# hex_schmitt_CMOS.net
KiCad netlist of a schematic drawn in EAGLE
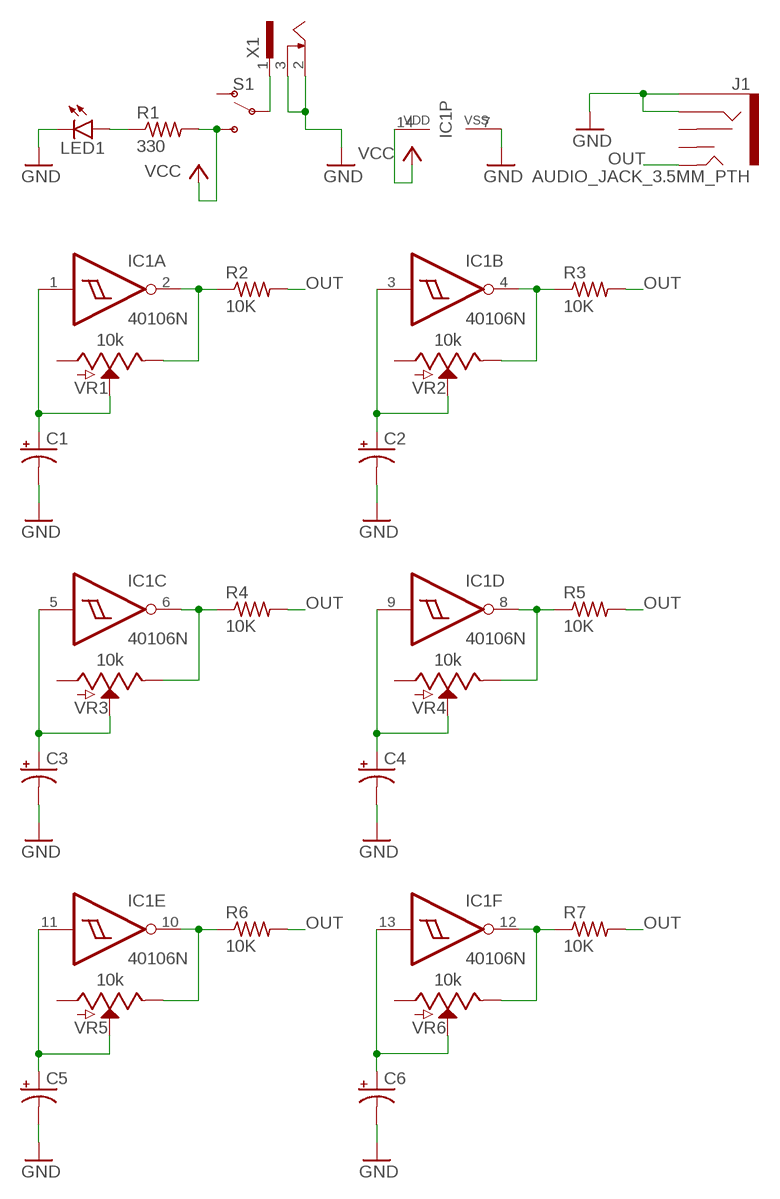
[diagram p0: schematic, sheet 1]

(export (version "E")
  (design (tool "Eeschema 10.0.6"))
  (components
    (comp (ref "C1")
      (value "CPOL-USE1.8-4")
      (footprint "eagle-import:E1,8-4")
      (libsource (lib "eagle-import") (part "CPOL-USE1.8-4"))
    )
    (comp (ref "C2")
      (value "CPOL-USE1.8-4")
      (footprint "eagle-import:E1,8-4")
      (libsource (lib "eagle-import") (part "CPOL-USE1.8-4"))
    )
    (comp (ref "C3")
      (value "CPOL-USE1.8-4")
      (footprint "eagle-import:E1,8-4")
      (libsource (lib "eagle-import") (part "CPOL-USE1.8-4"))
    )
    (comp (ref "C4")
      (value "CPOL-USE1.8-4")
      (footprint "eagle-import:E1,8-4")
      (libsource (lib "eagle-import") (part "CPOL-USE1.8-4"))
    )
    (comp (ref "C5")
      (value "CPOL-USE1.8-4")
      (footprint "eagle-import:E1,8-4")
      (libsource (lib "eagle-import") (part "CPOL-USE1.8-4"))
    )
    (comp (ref "C6")
      (value "CPOL-USE1.8-4")
      (footprint "eagle-import:E1,8-4")
      (libsource (lib "eagle-import") (part "CPOL-USE1.8-4"))
    )
    (comp (ref "IC1")
      (value "40106N")
      (footprint "eagle-import:DIL14")
      (libsource (lib "eagle-import") (part "40106N"))
    )
    (comp (ref "J1")
      (value "AUDIO_JACK_3.5MM_PTH")
      (footprint "eagle-import:AUDIO-JACK")
      (libsource (lib "eagle-import") (part "AUDIO_JACK_3.5MM_PTH"))
    )
    (comp (ref "LED1")
      (value "LED5MM")
      (footprint "eagle-import:LED5MM")
      (libsource (lib "eagle-import") (part "LED5MM"))
    )
    (comp (ref "R1")
      (value "330")
      (footprint "eagle-import:0204_5")
      (libsource (lib "eagle-import") (part "R-US_0204/5"))
    )
    (comp (ref "R2")
      (value "10K")
      (footprint "eagle-import:0204_5")
      (libsource (lib "eagle-import") (part "R-US_0204/5"))
    )
    (comp (ref "R3")
      (value "10K")
      (footprint "eagle-import:0204_5")
      (libsource (lib "eagle-import") (part "R-US_0204/5"))
    )
    (comp (ref "R4")
      (value "10K")
      (footprint "eagle-import:0204_5")
      (libsource (lib "eagle-import") (part "R-US_0204/5"))
    )
    (comp (ref "R5")
      (value "10K")
      (footprint "eagle-import:0204_5")
      (libsource (lib "eagle-import") (part "R-US_0204/5"))
    )
    (comp (ref "R6")
      (value "10K")
      (footprint "eagle-import:0204_5")
      (libsource (lib "eagle-import") (part "R-US_0204/5"))
    )
    (comp (ref "R7")
      (value "10K")
      (footprint "eagle-import:0204_5")
      (libsource (lib "eagle-import") (part "R-US_0204/5"))
    )
    (comp (ref "S1")
      (value "SWITCH-SPDT-PTH-11.6X4.0MM-LOCK")
      (footprint "eagle-import:SWITCH_SPDT_PTH_11.6X4.0MM_LOCK")
      (libsource (lib "eagle-import") (part "SWITCH-SPDT-PTH-11.6X4.0MM-LOCK"))
    )
    (comp (ref "VR1")
      (value "10k")
      (footprint "eagle-import:POT-PTH-ALPS")
      (libsource (lib "eagle-import") (part "POTENTIOMETER-PTH-9MM-1/20W-20%"))
    )
    (comp (ref "VR2")
      (value "10k")
      (footprint "eagle-import:POT-PTH-ALPS")
      (libsource (lib "eagle-import") (part "POTENTIOMETER-PTH-9MM-1/20W-20%"))
    )
    (comp (ref "VR3")
      (value "10k")
      (footprint "eagle-import:POT-PTH-ALPS")
      (libsource (lib "eagle-import") (part "POTENTIOMETER-PTH-9MM-1/20W-20%"))
    )
    (comp (ref "VR4")
      (value "10k")
      (footprint "eagle-import:POT-PTH-ALPS")
      (libsource (lib "eagle-import") (part "POTENTIOMETER-PTH-9MM-1/20W-20%"))
    )
    (comp (ref "VR5")
      (value "10k")
      (footprint "eagle-import:POT-PTH-ALPS")
      (libsource (lib "eagle-import") (part "POTENTIOMETER-PTH-9MM-1/20W-20%"))
    )
    (comp (ref "VR6")
      (value "10k")
      (footprint "eagle-import:POT-PTH-ALPS")
      (libsource (lib "eagle-import") (part "POTENTIOMETER-PTH-9MM-1/20W-20%"))
    )
    (comp (ref "X1")
      (value "SCD-014A")
      (footprint "eagle-import:SCD-014-A")
      (libsource (lib "eagle-import") (part "SCD-014A"))
    )
  )
  (nets
    (net (code "1") (name "/OUT") (class "Default")
      (node (ref "J1") (pin "TIP") (pinfunction "TIP_TIP") (pintype "bidirectional"))
      (node (ref "R2") (pin "2") (pinfunction "2_2") (pintype "passive"))
      (node (ref "R3") (pin "2") (pinfunction "2_2") (pintype "passive"))
      (node (ref "R4") (pin "2") (pinfunction "2_2") (pintype "passive"))
      (node (ref "R5") (pin "2") (pinfunction "2_2") (pintype "passive"))
      (node (ref "R6") (pin "2") (pinfunction "2_2") (pintype "passive"))
      (node (ref "R7") (pin "2") (pinfunction "2_2") (pintype "passive"))
    )
    (net (code "2") (name "GND") (class "Default")
      (node (ref "C1") (pin "-") (pinfunction "-_-") (pintype "passive"))
      (node (ref "C2") (pin "-") (pinfunction "-_-") (pintype "passive"))
      (node (ref "C3") (pin "-") (pinfunction "-_-") (pintype "passive"))
      (node (ref "C4") (pin "-") (pinfunction "-_-") (pintype "passive"))
      (node (ref "C5") (pin "-") (pinfunction "-_-") (pintype "passive"))
      (node (ref "C6") (pin "-") (pinfunction "-_-") (pintype "passive"))
      (node (ref "IC1") (pin "7") (pinfunction "VSS_7") (pintype "power_in"))
      (node (ref "J1") (pin "RING") (pinfunction "RING_RING") (pintype "bidirectional"))
      (node (ref "J1") (pin "SLEEVE") (pinfunction "SLEEVE_SLEEVE") (pintype "bidirectional"))
      (node (ref "LED1") (pin "K") (pinfunction "C_K") (pintype "passive"))
      (node (ref "X1") (pin "2") (pinfunction "2_2") (pintype "passive"))
      (node (ref "X1") (pin "3") (pinfunction "3_3") (pintype "passive"))
    )
    (net (code "3") (name "Net-(IC1A-I)") (class "Default")
      (node (ref "C1") (pin "+") (pinfunction "+_+") (pintype "passive"))
      (node (ref "IC1") (pin "1") (pinfunction "I_1") (pintype "input"))
      (node (ref "VR1") (pin "P$2") (pinfunction "S_P$2") (pintype "passive"))
    )
    (net (code "4") (name "Net-(IC1A-O)") (class "Default")
      (node (ref "IC1") (pin "2") (pinfunction "O_2") (pintype "output"))
      (node (ref "R2") (pin "1") (pinfunction "1_1") (pintype "passive"))
      (node (ref "VR1") (pin "P$1") (pinfunction "E_P$1") (pintype "passive"))
    )
    (net (code "5") (name "Net-(IC1B-I)") (class "Default")
      (node (ref "C2") (pin "+") (pinfunction "+_+") (pintype "passive"))
      (node (ref "IC1") (pin "3") (pinfunction "I_3") (pintype "input"))
      (node (ref "VR2") (pin "P$2") (pinfunction "S_P$2") (pintype "passive"))
    )
    (net (code "6") (name "Net-(IC1B-O)") (class "Default")
      (node (ref "IC1") (pin "4") (pinfunction "O_4") (pintype "output"))
      (node (ref "R3") (pin "1") (pinfunction "1_1") (pintype "passive"))
      (node (ref "VR2") (pin "P$1") (pinfunction "E_P$1") (pintype "passive"))
    )
    (net (code "7") (name "Net-(IC1C-I)") (class "Default")
      (node (ref "C3") (pin "+") (pinfunction "+_+") (pintype "passive"))
      (node (ref "IC1") (pin "5") (pinfunction "I_5") (pintype "input"))
      (node (ref "VR3") (pin "P$2") (pinfunction "S_P$2") (pintype "passive"))
    )
    (net (code "8") (name "Net-(IC1C-O)") (class "Default")
      (node (ref "IC1") (pin "6") (pinfunction "O_6") (pintype "output"))
      (node (ref "R4") (pin "1") (pinfunction "1_1") (pintype "passive"))
      (node (ref "VR3") (pin "P$1") (pinfunction "E_P$1") (pintype "passive"))
    )
    (net (code "9") (name "Net-(IC1D-I)") (class "Default")
      (node (ref "C4") (pin "+") (pinfunction "+_+") (pintype "passive"))
      (node (ref "IC1") (pin "9") (pinfunction "I_9") (pintype "input"))
      (node (ref "VR4") (pin "P$2") (pinfunction "S_P$2") (pintype "passive"))
    )
    (net (code "10") (name "Net-(IC1D-O)") (class "Default")
      (node (ref "IC1") (pin "8") (pinfunction "O_8") (pintype "output"))
      (node (ref "R5") (pin "1") (pinfunction "1_1") (pintype "passive"))
      (node (ref "VR4") (pin "P$1") (pinfunction "E_P$1") (pintype "passive"))
    )
    (net (code "11") (name "Net-(IC1E-I)") (class "Default")
      (node (ref "C5") (pin "+") (pinfunction "+_+") (pintype "passive"))
      (node (ref "IC1") (pin "11") (pinfunction "I_11") (pintype "input"))
      (node (ref "VR5") (pin "P$2") (pinfunction "S_P$2") (pintype "passive"))
    )
    (net (code "12") (name "Net-(IC1E-O)") (class "Default")
      (node (ref "IC1") (pin "10") (pinfunction "O_10") (pintype "output"))
      (node (ref "R6") (pin "1") (pinfunction "1_1") (pintype "passive"))
      (node (ref "VR5") (pin "P$1") (pinfunction "E_P$1") (pintype "passive"))
    )
    (net (code "13") (name "Net-(IC1F-I)") (class "Default")
      (node (ref "C6") (pin "+") (pinfunction "+_+") (pintype "passive"))
      (node (ref "IC1") (pin "13") (pinfunction "I_13") (pintype "input"))
      (node (ref "VR6") (pin "P$2") (pinfunction "S_P$2") (pintype "passive"))
    )
    (net (code "14") (name "Net-(IC1F-O)") (class "Default")
      (node (ref "IC1") (pin "12") (pinfunction "O_12") (pintype "output"))
      (node (ref "R7") (pin "1") (pinfunction "1_1") (pintype "passive"))
      (node (ref "VR6") (pin "P$1") (pinfunction "E_P$1") (pintype "passive"))
    )
    (net (code "15") (name "Net-(LED1-PadA)") (class "Default")
      (node (ref "LED1") (pin "A") (pinfunction "A_A") (pintype "passive"))
      (node (ref "R1") (pin "1") (pinfunction "1_1") (pintype "passive"))
    )
    (net (code "16") (name "Net-(S1-P)") (class "Default")
      (node (ref "S1") (pin "2") (pinfunction "P_2") (pintype "passive"))
      (node (ref "X1") (pin "1") (pinfunction "1_1") (pintype "passive"))
    )
    (net (code "17") (name "VCC") (class "Default")
      (node (ref "IC1") (pin "14") (pinfunction "VDD_14") (pintype "power_in"))
      (node (ref "R1") (pin "2") (pinfunction "2_2") (pintype "passive"))
      (node (ref "S1") (pin "3") (pinfunction "S_3") (pintype "passive"))
    )
    (net (code "18") (name "unconnected-(J1-PadRSH)") (class "Default")
      (node (ref "J1") (pin "RSH") (pinfunction "RSH_RSH") (pintype "bidirectional"))
    )
    (net (code "19") (name "unconnected-(J1-PadTSH)") (class "Default")
      (node (ref "J1") (pin "TSH") (pinfunction "TSH_TSH") (pintype "bidirectional"))
    )
    (net (code "20") (name "unconnected-(S1-O-Pad1)") (class "Default")
      (node (ref "S1") (pin "1") (pinfunction "O_1") (pintype "passive"))
    )
    (net (code "21") (name "unconnected-(VR1-A-PadP$3)") (class "Default")
      (node (ref "VR1") (pin "P$3") (pinfunction "A_P$3") (pintype "passive"))
    )
    (net (code "22") (name "unconnected-(VR2-A-PadP$3)") (class "Default")
      (node (ref "VR2") (pin "P$3") (pinfunction "A_P$3") (pintype "passive"))
    )
    (net (code "23") (name "unconnected-(VR3-A-PadP$3)") (class "Default")
      (node (ref "VR3") (pin "P$3") (pinfunction "A_P$3") (pintype "passive"))
    )
    (net (code "24") (name "unconnected-(VR4-A-PadP$3)") (class "Default")
      (node (ref "VR4") (pin "P$3") (pinfunction "A_P$3") (pintype "passive"))
    )
    (net (code "25") (name "unconnected-(VR5-A-PadP$3)") (class "Default")
      (node (ref "VR5") (pin "P$3") (pinfunction "A_P$3") (pintype "passive"))
    )
    (net (code "26") (name "unconnected-(VR6-A-PadP$3)") (class "Default")
      (node (ref "VR6") (pin "P$3") (pinfunction "A_P$3") (pintype "passive"))
    )
  )
)
